# Adafruit_AT42QT1010_Breakout.net
KiCad netlist of a schematic drawn in EAGLE
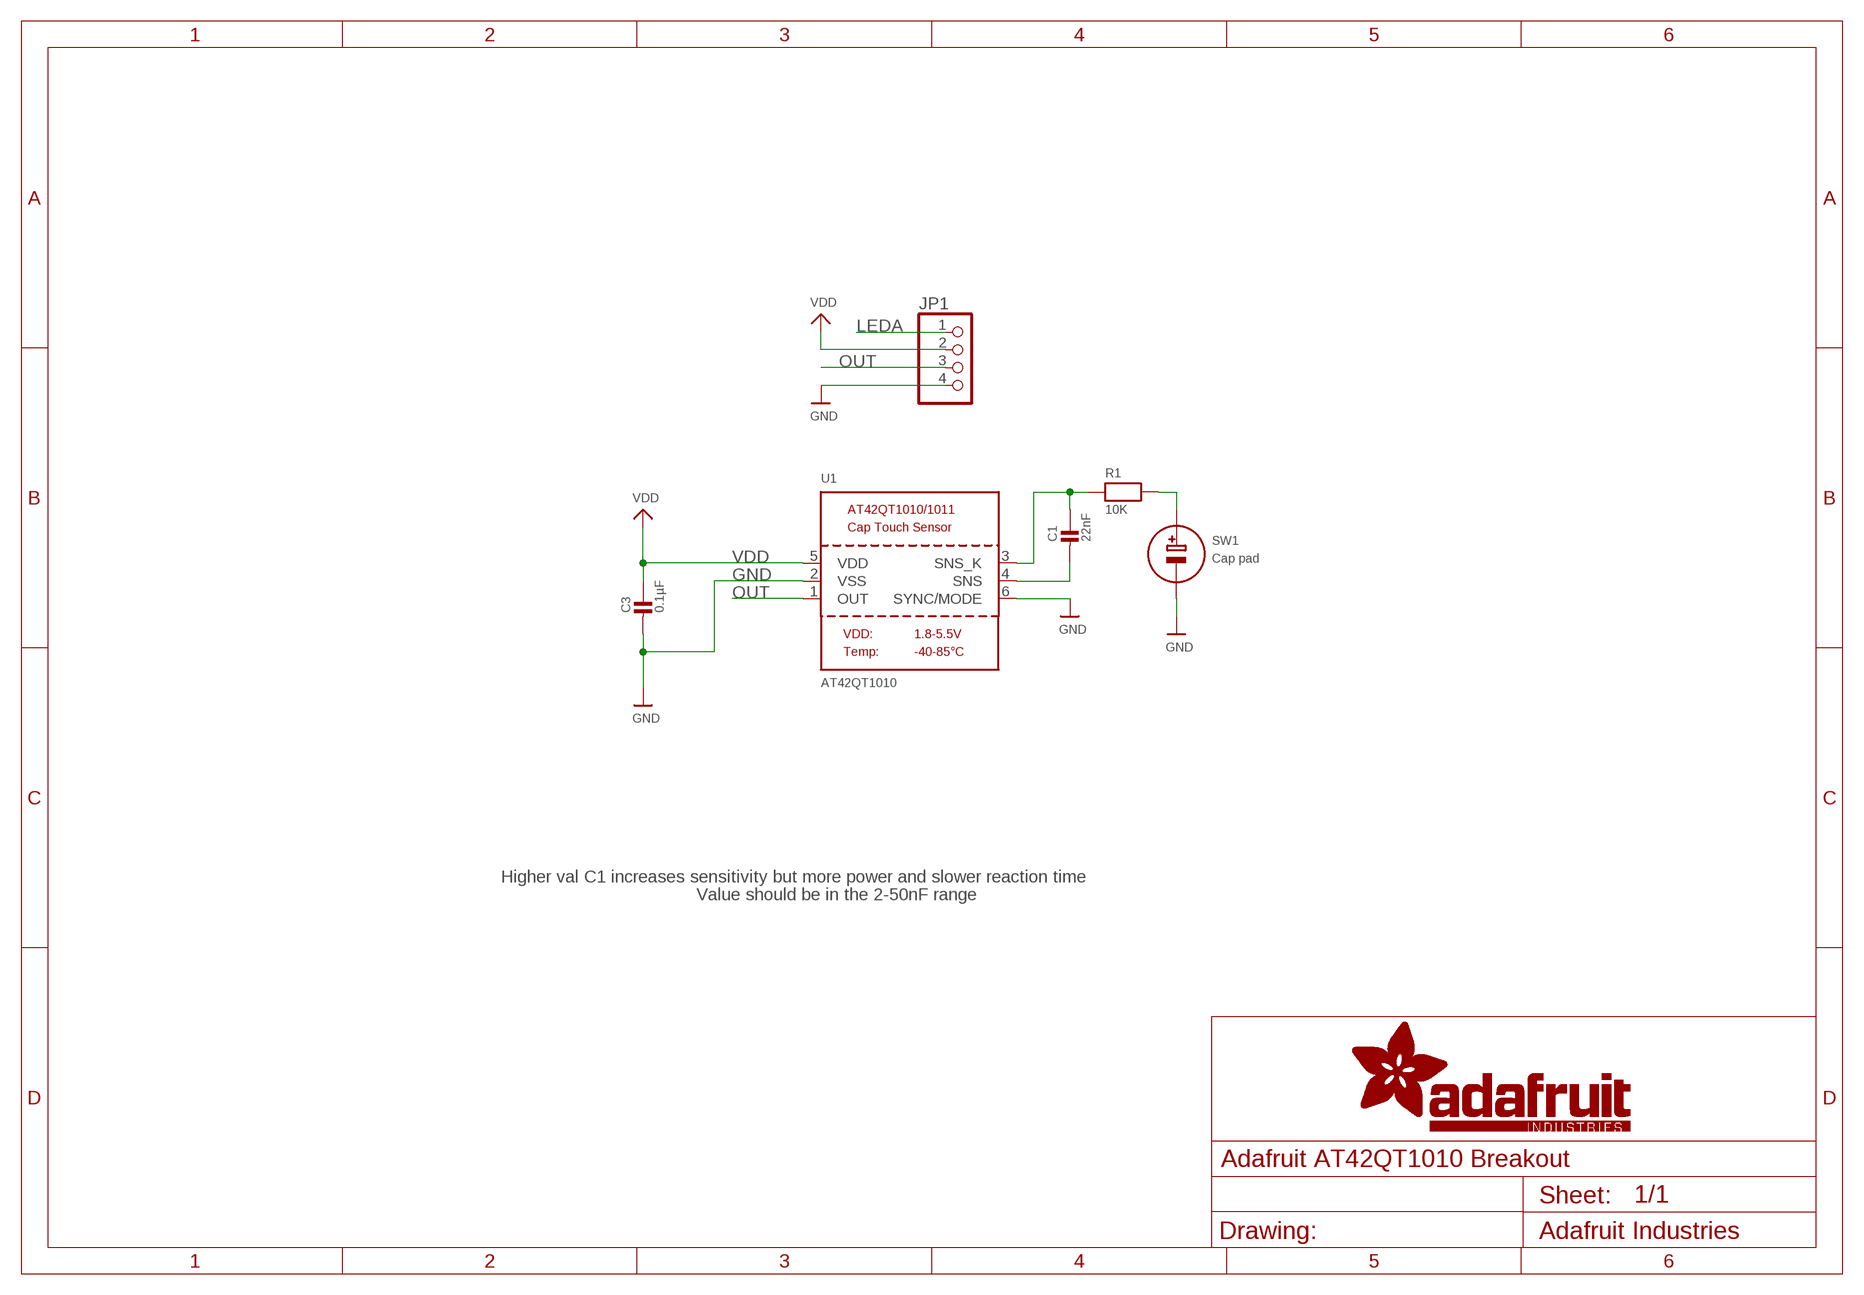
[diagram p0: schematic, sheet 1]

(export (version "E")
  (design (tool "Eeschema 10.0.6"))
  (components
    (comp (ref "C1")
      (value "22nF")
      (footprint "eagle-import:_0805")
      (libsource (lib "eagle-import") (part "CAP_CERAMIC_0805"))
    )
    (comp (ref "C3")
      (value "0.1µF")
      (footprint "eagle-import:_0805")
      (libsource (lib "eagle-import") (part "CAP_CERAMIC_0805"))
    )
    (comp (ref "JP1")
      (value "HEADER-1X476MIL")
      (footprint "eagle-import:1X04_ROUND_76")
      (libsource (lib "eagle-import") (part "HEADER-1X476MIL"))
    )
    (comp (ref "R1")
      (value "10K")
      (footprint "eagle-import:_0805")
      (libsource (lib "eagle-import") (part "RESISTOR_0805"))
    )
    (comp (ref "SW1")
      (value "Cap pad")
      (footprint "eagle-import:CAPTOUCH_SIMPLE_12.5MM")
      (libsource (lib "eagle-import") (part "SWITCH_CAPTOUCHATMELAT42QT"))
    )
    (comp (ref "U1")
      (value "AT42QT1010")
      (footprint "eagle-import:SOT23-6")
      (libsource (lib "eagle-import") (part "AT42QT1010/1"))
    )
  )
  (nets
    (net (code "1") (name "/LEDA") (class "Default")
      (node (ref "JP1") (pin "1") (pinfunction "1_1") (pintype "passive"))
    )
    (net (code "2") (name "/OUT") (class "Default")
      (node (ref "JP1") (pin "3") (pinfunction "3_3") (pintype "passive"))
      (node (ref "U1") (pin "1") (pinfunction "OUT_1") (pintype "output"))
    )
    (net (code "3") (name "GND") (class "Default")
      (node (ref "C3") (pin "2") (pinfunction "P$2_2") (pintype "passive"))
      (node (ref "JP1") (pin "4") (pinfunction "4_4") (pintype "passive"))
      (node (ref "SW1") (pin "G") (pinfunction "-_G") (pintype "passive"))
      (node (ref "U1") (pin "2") (pinfunction "VSS_2") (pintype "power_in"))
      (node (ref "U1") (pin "6") (pinfunction "SYNC/MODE_6") (pintype "input"))
    )
    (net (code "4") (name "Net-(C1-P$1)") (class "Default")
      (node (ref "C1") (pin "1") (pinfunction "P$1_1") (pintype "passive"))
      (node (ref "R1") (pin "1") (pinfunction "1_1") (pintype "passive"))
      (node (ref "U1") (pin "3") (pinfunction "SNS_K_3") (pintype "bidirectional"))
    )
    (net (code "5") (name "Net-(C1-P$2)") (class "Default")
      (node (ref "C1") (pin "2") (pinfunction "P$2_2") (pintype "passive"))
      (node (ref "U1") (pin "4") (pinfunction "SNS_4") (pintype "bidirectional"))
    )
    (net (code "6") (name "Net-(SW1-+)") (class "Default")
      (node (ref "R1") (pin "2") (pinfunction "2_2") (pintype "passive"))
      (node (ref "SW1") (pin "E") (pinfunction "+_E") (pintype "passive"))
    )
    (net (code "7") (name "VDD") (class "Default")
      (node (ref "C3") (pin "1") (pinfunction "P$1_1") (pintype "passive"))
      (node (ref "JP1") (pin "2") (pinfunction "2_2") (pintype "passive"))
      (node (ref "U1") (pin "5") (pinfunction "VDD_5") (pintype "power_in"))
    )
  )
)
